# communication-hub.net
KiCad netlist of a schematic drawn in EAGLE
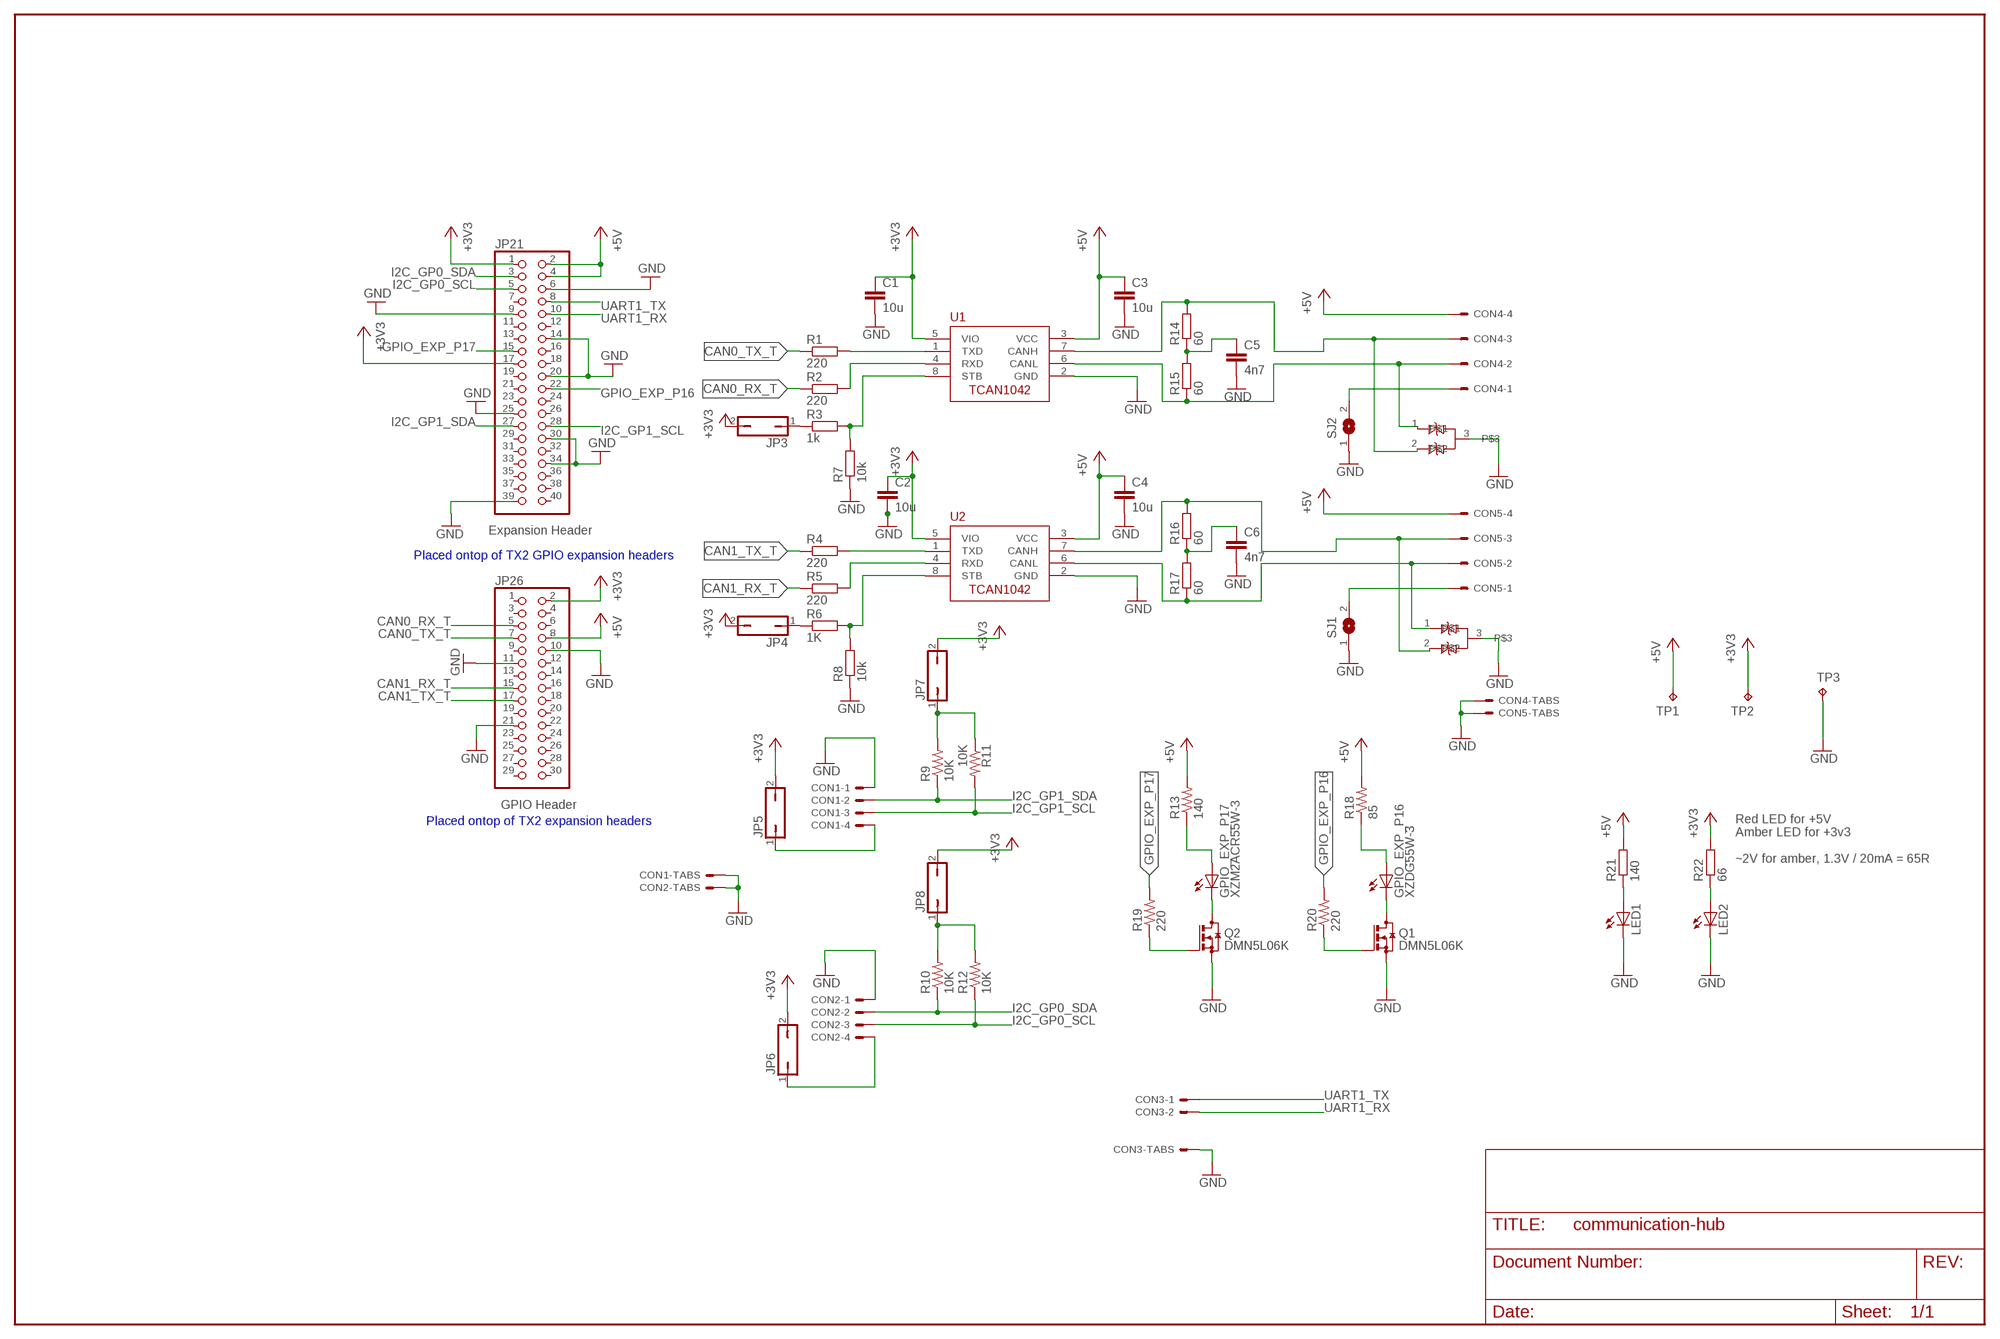
[diagram p0: schematic, sheet 1]

(export (version "E")
  (design (tool "Eeschema 10.0.6"))
  (components
    (comp (ref "C1")
      (value "10u")
      (footprint "eagle-import:C0805")
      (libsource (lib "eagle-import") (part "C-EUC0805"))
    )
    (comp (ref "C2")
      (value "10u")
      (footprint "eagle-import:C0805")
      (libsource (lib "eagle-import") (part "C-EUC0805"))
    )
    (comp (ref "C3")
      (value "10u")
      (footprint "eagle-import:C0805")
      (libsource (lib "eagle-import") (part "C-EUC0805"))
    )
    (comp (ref "C4")
      (value "10u")
      (footprint "eagle-import:C0805")
      (libsource (lib "eagle-import") (part "C-EUC0805"))
    )
    (comp (ref "C5")
      (value "4n7")
      (footprint "eagle-import:C0805")
      (libsource (lib "eagle-import") (part "C-EUC0805"))
    )
    (comp (ref "C6")
      (value "4n7")
      (footprint "eagle-import:C0805")
      (libsource (lib "eagle-import") (part "C-EUC0805"))
    )
    (comp (ref "CON1")
      (value "SM04B-GHS-TB")
      (footprint "eagle-import:SM04B-GHS-TB")
      (libsource (lib "eagle-import") (part "SM04B-GHS-TB"))
    )
    (comp (ref "CON2")
      (value "SM04B-GHS-TB")
      (footprint "eagle-import:SM04B-GHS-TB")
      (libsource (lib "eagle-import") (part "SM04B-GHS-TB"))
    )
    (comp (ref "CON3")
      (value "SM02B-GHS-TB")
      (footprint "eagle-import:SM02B-GHS-TB")
      (libsource (lib "eagle-import") (part "SM02B-GHS-TB"))
    )
    (comp (ref "CON4")
      (value "SM04B-GHS-TB")
      (footprint "eagle-import:SM04B-GHS-TB")
      (libsource (lib "eagle-import") (part "SM04B-GHS-TB"))
    )
    (comp (ref "CON5")
      (value "SM04B-GHS-TB")
      (footprint "eagle-import:SM04B-GHS-TB")
      (libsource (lib "eagle-import") (part "SM04B-GHS-TB"))
    )
    (comp (ref "GPIO_EXP_P16")
      (value "XZDG55W-3")
      (footprint "eagle-import:LED_1206")
      (libsource (lib "eagle-import") (part "LED_E"))
    )
    (comp (ref "GPIO_EXP_P17")
      (value "XZM2ACR55W-3")
      (footprint "eagle-import:LED_1206")
      (libsource (lib "eagle-import") (part "LED_E"))
    )
    (comp (ref "JP3")
      (value "JP1Q")
      (footprint "eagle-import:JP1")
      (libsource (lib "eagle-import") (part "JP1Q"))
    )
    (comp (ref "JP4")
      (value "JP1Q")
      (footprint "eagle-import:JP1")
      (libsource (lib "eagle-import") (part "JP1Q"))
    )
    (comp (ref "JP5")
      (value "JP1Q")
      (footprint "eagle-import:JP1")
      (libsource (lib "eagle-import") (part "JP1Q"))
    )
    (comp (ref "JP6")
      (value "JP1Q")
      (footprint "eagle-import:JP1")
      (libsource (lib "eagle-import") (part "JP1Q"))
    )
    (comp (ref "JP7")
      (value "JP1Q")
      (footprint "eagle-import:JP1")
      (libsource (lib "eagle-import") (part "JP1Q"))
    )
    (comp (ref "JP8")
      (value "JP1Q")
      (footprint "eagle-import:JP1")
      (libsource (lib "eagle-import") (part "JP1Q"))
    )
    (comp (ref "JP21")
      (value "PINHD-2X20")
      (footprint "eagle-import:2X20")
      (libsource (lib "eagle-import") (part "PINHD-2X20"))
    )
    (comp (ref "JP26")
      (value "PINHD-2X15")
      (footprint "eagle-import:2X15")
      (libsource (lib "eagle-import") (part "PINHD-2X15"))
    )
    (comp (ref "LED1")
      (value "LEDSMT1206")
      (footprint "eagle-import:1206")
      (libsource (lib "eagle-import") (part "LEDSMT1206"))
    )
    (comp (ref "LED2")
      (value "LEDSMT1206")
      (footprint "eagle-import:1206")
      (libsource (lib "eagle-import") (part "LEDSMT1206"))
    )
    (comp (ref "Q1")
      (value "DMN5L06K")
      (footprint "eagle-import:SOT23")
      (libsource (lib "eagle-import") (part "BSS123"))
    )
    (comp (ref "Q2")
      (value "DMN5L06K")
      (footprint "eagle-import:SOT23")
      (libsource (lib "eagle-import") (part "BSS123"))
    )
    (comp (ref "R1")
      (value "220")
      (footprint "eagle-import:R0805")
      (libsource (lib "eagle-import") (part "R-EU_R0805"))
    )
    (comp (ref "R2")
      (value "220")
      (footprint "eagle-import:R0805")
      (libsource (lib "eagle-import") (part "R-EU_R0805"))
    )
    (comp (ref "R3")
      (value "1k")
      (footprint "eagle-import:R0805")
      (libsource (lib "eagle-import") (part "R-EU_R0805"))
    )
    (comp (ref "R4")
      (value "220")
      (footprint "eagle-import:R0805")
      (libsource (lib "eagle-import") (part "R-EU_R0805"))
    )
    (comp (ref "R5")
      (value "220")
      (footprint "eagle-import:R0805")
      (libsource (lib "eagle-import") (part "R-EU_R0805"))
    )
    (comp (ref "R6")
      (value "1K")
      (footprint "eagle-import:R0805")
      (libsource (lib "eagle-import") (part "R-EU_R0805"))
    )
    (comp (ref "R7")
      (value "10k")
      (footprint "eagle-import:R0805")
      (libsource (lib "eagle-import") (part "R-EU_R0805"))
    )
    (comp (ref "R8")
      (value "10k")
      (footprint "eagle-import:R0805")
      (libsource (lib "eagle-import") (part "R-EU_R0805"))
    )
    (comp (ref "R9")
      (value "10K")
      (footprint "eagle-import:M1206")
      (libsource (lib "eagle-import") (part "resistor_348_R-US_M1206"))
    )
    (comp (ref "R10")
      (value "10K")
      (footprint "eagle-import:M1206")
      (libsource (lib "eagle-import") (part "resistor_348_R-US_M1206"))
    )
    (comp (ref "R11")
      (value "10K")
      (footprint "eagle-import:M1206")
      (libsource (lib "eagle-import") (part "resistor_348_R-US_M1206"))
    )
    (comp (ref "R12")
      (value "10K")
      (footprint "eagle-import:M1206")
      (libsource (lib "eagle-import") (part "resistor_348_R-US_M1206"))
    )
    (comp (ref "R13")
      (value "140")
      (footprint "eagle-import:M1206")
      (libsource (lib "eagle-import") (part "resistor_348_R-US_M1206"))
    )
    (comp (ref "R14")
      (value "60")
      (footprint "eagle-import:R1206")
      (libsource (lib "eagle-import") (part "R-EU_R1206"))
    )
    (comp (ref "R15")
      (value "60")
      (footprint "eagle-import:R1206")
      (libsource (lib "eagle-import") (part "R-EU_R1206"))
    )
    (comp (ref "R16")
      (value "60")
      (footprint "eagle-import:R1206")
      (libsource (lib "eagle-import") (part "R-EU_R1206"))
    )
    (comp (ref "R17")
      (value "60")
      (footprint "eagle-import:R1206")
      (libsource (lib "eagle-import") (part "R-EU_R1206"))
    )
    (comp (ref "R18")
      (value "85")
      (footprint "eagle-import:M1206")
      (libsource (lib "eagle-import") (part "resistor_348_R-US_M1206"))
    )
    (comp (ref "R19")
      (value "220")
      (footprint "eagle-import:R0805")
      (libsource (lib "eagle-import") (part "R-US_R0805"))
    )
    (comp (ref "R20")
      (value "220")
      (footprint "eagle-import:R0805")
      (libsource (lib "eagle-import") (part "R-US_R0805"))
    )
    (comp (ref "R21")
      (value "140")
      (footprint "eagle-import:R0805")
      (libsource (lib "eagle-import") (part "R-EU_R0805"))
    )
    (comp (ref "R22")
      (value "66")
      (footprint "eagle-import:R0805")
      (libsource (lib "eagle-import") (part "R-EU_R0805"))
    )
    (comp (ref "SJ1") (value "SJ") (footprint "eagle-import:SJ") (libsource (lib "eagle-import") (part "SJ")))
    (comp (ref "SJ2") (value "SJ") (footprint "eagle-import:SJ") (libsource (lib "eagle-import") (part "SJ")))
    (comp (ref "TP1")
      (value "TPB2,54")
      (footprint "eagle-import:B2,54")
      (libsource (lib "eagle-import") (part "TPB2,54"))
    )
    (comp (ref "TP2")
      (value "TPB2,54")
      (footprint "eagle-import:B2,54")
      (libsource (lib "eagle-import") (part "TPB2,54"))
    )
    (comp (ref "TP3")
      (value "TPB2,54")
      (footprint "eagle-import:B2,54")
      (libsource (lib "eagle-import") (part "TPB2,54"))
    )
    (comp (ref "U$4")
      (value "NUP2105L")
      (footprint "eagle-import:SOT23")
      (libsource (lib "eagle-import") (part "NUP2105L"))
    )
    (comp (ref "U$5")
      (value "NUP2105L")
      (footprint "eagle-import:SOT23")
      (libsource (lib "eagle-import") (part "NUP2105L"))
    )
    (comp (ref "U1")
      (value "TCAN1042HVDR")
      (footprint "eagle-import:SO-8")
      (libsource (lib "eagle-import") (part "TCAN1042HVDR"))
    )
    (comp (ref "U2")
      (value "TCAN1042HVDR")
      (footprint "eagle-import:SO-8")
      (libsource (lib "eagle-import") (part "TCAN1042HVDR"))
    )
  )
  (nets
    (net (code "1") (name "+3V3") (class "Default")
      (node (ref "C1") (pin "1") (pinfunction "1_1") (pintype "passive"))
      (node (ref "C2") (pin "1") (pinfunction "1_1") (pintype "passive"))
      (node (ref "JP21") (pin "1") (pinfunction "1_1") (pintype "passive"))
      (node (ref "JP21") (pin "17") (pinfunction "17_17") (pintype "passive"))
      (node (ref "JP26") (pin "2") (pinfunction "2_2") (pintype "passive"))
      (node (ref "JP3") (pin "2") (pinfunction "2_2") (pintype "passive"))
      (node (ref "JP4") (pin "2") (pinfunction "2_2") (pintype "passive"))
      (node (ref "JP5") (pin "2") (pinfunction "2_2") (pintype "passive"))
      (node (ref "JP6") (pin "2") (pinfunction "2_2") (pintype "passive"))
      (node (ref "JP7") (pin "2") (pinfunction "2_2") (pintype "passive"))
      (node (ref "JP8") (pin "2") (pinfunction "2_2") (pintype "passive"))
      (node (ref "R22") (pin "2") (pinfunction "2_2") (pintype "passive"))
      (node (ref "TP2") (pin "TP") (pinfunction "TP_TP") (pintype "input"))
      (node (ref "U1") (pin "5") (pinfunction "VIO_5") (pintype "bidirectional"))
      (node (ref "U2") (pin "5") (pinfunction "VIO_5") (pintype "bidirectional"))
    )
    (net (code "2") (name "+5V") (class "Default")
      (node (ref "C3") (pin "1") (pinfunction "1_1") (pintype "passive"))
      (node (ref "C4") (pin "1") (pinfunction "1_1") (pintype "passive"))
      (node (ref "CON4") (pin "P$4") (pinfunction "S_P$4") (pintype "passive"))
      (node (ref "CON5") (pin "P$4") (pinfunction "S_P$4") (pintype "passive"))
      (node (ref "JP21") (pin "2") (pinfunction "2_2") (pintype "passive"))
      (node (ref "JP21") (pin "4") (pinfunction "4_4") (pintype "passive"))
      (node (ref "JP26") (pin "8") (pinfunction "8_8") (pintype "passive"))
      (node (ref "R13") (pin "2") (pinfunction "2_2") (pintype "passive"))
      (node (ref "R18") (pin "2") (pinfunction "2_2") (pintype "passive"))
      (node (ref "R21") (pin "2") (pinfunction "2_2") (pintype "passive"))
      (node (ref "TP1") (pin "TP") (pinfunction "TP_TP") (pintype "input"))
      (node (ref "U1") (pin "3") (pinfunction "VCC_3") (pintype "bidirectional"))
      (node (ref "U2") (pin "3") (pinfunction "VCC_3") (pintype "bidirectional"))
    )
    (net (code "3") (name "/I2C_GP0_SCL") (class "Default")
      (node (ref "CON2") (pin "P$3") (pinfunction "S_P$3") (pintype "passive"))
      (node (ref "JP21") (pin "5") (pinfunction "5_5") (pintype "passive"))
      (node (ref "R12") (pin "1") (pinfunction "1_1") (pintype "passive"))
    )
    (net (code "4") (name "/I2C_GP0_SDA") (class "Default")
      (node (ref "CON2") (pin "P$2") (pinfunction "S_P$2") (pintype "passive"))
      (node (ref "JP21") (pin "3") (pinfunction "3_3") (pintype "passive"))
      (node (ref "R10") (pin "1") (pinfunction "1_1") (pintype "passive"))
    )
    (net (code "5") (name "/I2C_GP1_SCL") (class "Default")
      (node (ref "CON1") (pin "P$3") (pinfunction "S_P$3") (pintype "passive"))
      (node (ref "JP21") (pin "28") (pinfunction "28_28") (pintype "passive"))
      (node (ref "R11") (pin "2") (pinfunction "2_2") (pintype "passive"))
    )
    (net (code "6") (name "/I2C_GP1_SDA") (class "Default")
      (node (ref "CON1") (pin "P$2") (pinfunction "S_P$2") (pintype "passive"))
      (node (ref "JP21") (pin "27") (pinfunction "27_27") (pintype "passive"))
      (node (ref "R9") (pin "1") (pinfunction "1_1") (pintype "passive"))
    )
    (net (code "7") (name "/UART1_RX") (class "Default")
      (node (ref "CON3") (pin "P$2") (pinfunction "S_P$2") (pintype "passive"))
      (node (ref "JP21") (pin "10") (pinfunction "10_10") (pintype "passive"))
    )
    (net (code "8") (name "/UART1_TX") (class "Default")
      (node (ref "CON3") (pin "P$1") (pinfunction "S_P$1") (pintype "passive"))
      (node (ref "JP21") (pin "8") (pinfunction "8_8") (pintype "passive"))
    )
    (net (code "9") (name "CAN0_RX_T") (class "Default")
      (node (ref "JP26") (pin "5") (pinfunction "5_5") (pintype "passive"))
      (node (ref "R2") (pin "1") (pinfunction "1_1") (pintype "passive"))
    )
    (net (code "10") (name "CAN0_TX_T") (class "Default")
      (node (ref "JP26") (pin "7") (pinfunction "7_7") (pintype "passive"))
      (node (ref "R1") (pin "1") (pinfunction "1_1") (pintype "passive"))
    )
    (net (code "11") (name "CAN1_RX_T") (class "Default")
      (node (ref "JP26") (pin "15") (pinfunction "15_15") (pintype "passive"))
      (node (ref "R5") (pin "1") (pinfunction "1_1") (pintype "passive"))
    )
    (net (code "12") (name "CAN1_TX_T") (class "Default")
      (node (ref "JP26") (pin "17") (pinfunction "17_17") (pintype "passive"))
      (node (ref "R4") (pin "1") (pinfunction "1_1") (pintype "passive"))
    )
    (net (code "13") (name "GND") (class "Default")
      (node (ref "C1") (pin "2") (pinfunction "2_2") (pintype "passive"))
      (node (ref "C2") (pin "2") (pinfunction "2_2") (pintype "passive"))
      (node (ref "C3") (pin "2") (pinfunction "2_2") (pintype "passive"))
      (node (ref "C4") (pin "2") (pinfunction "2_2") (pintype "passive"))
      (node (ref "C5") (pin "2") (pinfunction "2_2") (pintype "passive"))
      (node (ref "C6") (pin "2") (pinfunction "2_2") (pintype "passive"))
      (node (ref "CON1") (pin "P$1") (pinfunction "S_P$1") (pintype "passive"))
      (node (ref "CON1") (pin "P$5") (pinfunction "S_P$5") (pintype "passive"))
      (node (ref "CON1") (pin "P$6") (pinfunction "S_P$6") (pintype "passive"))
      (node (ref "CON2") (pin "P$1") (pinfunction "S_P$1") (pintype "passive"))
      (node (ref "CON2") (pin "P$5") (pinfunction "S_P$5") (pintype "passive"))
      (node (ref "CON2") (pin "P$6") (pinfunction "S_P$6") (pintype "passive"))
      (node (ref "CON3") (pin "P$3") (pinfunction "S_P$3") (pintype "passive"))
      (node (ref "CON3") (pin "P$4") (pinfunction "S_P$4") (pintype "passive"))
      (node (ref "CON4") (pin "P$5") (pinfunction "S_P$5") (pintype "passive"))
      (node (ref "CON4") (pin "P$6") (pinfunction "S_P$6") (pintype "passive"))
      (node (ref "CON5") (pin "P$5") (pinfunction "S_P$5") (pintype "passive"))
      (node (ref "CON5") (pin "P$6") (pinfunction "S_P$6") (pintype "passive"))
      (node (ref "JP21") (pin "14") (pinfunction "14_14") (pintype "passive"))
      (node (ref "JP21") (pin "20") (pinfunction "20_20") (pintype "passive"))
      (node (ref "JP21") (pin "25") (pinfunction "25_25") (pintype "passive"))
      (node (ref "JP21") (pin "30") (pinfunction "30_30") (pintype "passive"))
      (node (ref "JP21") (pin "34") (pinfunction "34_34") (pintype "passive"))
      (node (ref "JP21") (pin "39") (pinfunction "39_39") (pintype "passive"))
      (node (ref "JP21") (pin "6") (pinfunction "6_6") (pintype "passive"))
      (node (ref "JP21") (pin "9") (pinfunction "9_9") (pintype "passive"))
      (node (ref "JP26") (pin "10") (pinfunction "10_10") (pintype "passive"))
      (node (ref "JP26") (pin "11") (pinfunction "11_11") (pintype "passive"))
      (node (ref "JP26") (pin "21") (pinfunction "21_21") (pintype "passive"))
      (node (ref "LED1") (pin "C") (pinfunction "C_C") (pintype "passive"))
      (node (ref "LED2") (pin "C") (pinfunction "C_C") (pintype "passive"))
      (node (ref "Q1") (pin "2") (pinfunction "S_2") (pintype "passive"))
      (node (ref "Q2") (pin "2") (pinfunction "S_2") (pintype "passive"))
      (node (ref "R7") (pin "1") (pinfunction "1_1") (pintype "passive"))
      (node (ref "R8") (pin "1") (pinfunction "1_1") (pintype "passive"))
      (node (ref "SJ1") (pin "1") (pinfunction "1_1") (pintype "passive"))
      (node (ref "SJ2") (pin "1") (pinfunction "1_1") (pintype "passive"))
      (node (ref "TP3") (pin "TP") (pinfunction "TP_TP") (pintype "input"))
      (node (ref "U$4") (pin "3") (pinfunction "P$3_3") (pintype "bidirectional"))
      (node (ref "U$5") (pin "3") (pinfunction "P$3_3") (pintype "bidirectional"))
      (node (ref "U1") (pin "2") (pinfunction "GND_2") (pintype "bidirectional"))
      (node (ref "U2") (pin "2") (pinfunction "GND_2") (pintype "bidirectional"))
    )
    (net (code "14") (name "GPIO_EXP_P16") (class "Default")
      (node (ref "JP21") (pin "22") (pinfunction "22_22") (pintype "passive"))
      (node (ref "R20") (pin "2") (pinfunction "2_2") (pintype "passive"))
    )
    (net (code "15") (name "GPIO_EXP_P17") (class "Default")
      (node (ref "JP21") (pin "15") (pinfunction "15_15") (pintype "passive"))
      (node (ref "R19") (pin "2") (pinfunction "2_2") (pintype "passive"))
    )
    (net (code "16") (name "Net-(C5-Pad1)") (class "Default")
      (node (ref "C5") (pin "1") (pinfunction "1_1") (pintype "passive"))
      (node (ref "R14") (pin "1") (pinfunction "1_1") (pintype "passive"))
      (node (ref "R15") (pin "2") (pinfunction "2_2") (pintype "passive"))
    )
    (net (code "17") (name "Net-(C6-Pad1)") (class "Default")
      (node (ref "C6") (pin "1") (pinfunction "1_1") (pintype "passive"))
      (node (ref "R16") (pin "1") (pinfunction "1_1") (pintype "passive"))
      (node (ref "R17") (pin "2") (pinfunction "2_2") (pintype "passive"))
    )
    (net (code "18") (name "Net-(CON1D-S)") (class "Default")
      (node (ref "CON1") (pin "P$4") (pinfunction "S_P$4") (pintype "passive"))
      (node (ref "JP5") (pin "1") (pinfunction "1_1") (pintype "passive"))
    )
    (net (code "19") (name "Net-(CON2D-S)") (class "Default")
      (node (ref "CON2") (pin "P$4") (pinfunction "S_P$4") (pintype "passive"))
      (node (ref "JP6") (pin "1") (pinfunction "1_1") (pintype "passive"))
    )
    (net (code "20") (name "Net-(CON4A-S)") (class "Default")
      (node (ref "CON4") (pin "P$1") (pinfunction "S_P$1") (pintype "passive"))
      (node (ref "SJ2") (pin "2") (pinfunction "2_2") (pintype "passive"))
    )
    (net (code "21") (name "Net-(CON4B-S)") (class "Default")
      (node (ref "CON4") (pin "P$2") (pinfunction "S_P$2") (pintype "passive"))
      (node (ref "R15") (pin "1") (pinfunction "1_1") (pintype "passive"))
      (node (ref "U$4") (pin "1") (pinfunction "P$1_1") (pintype "bidirectional"))
      (node (ref "U1") (pin "6") (pinfunction "CANL_6") (pintype "bidirectional"))
    )
    (net (code "22") (name "Net-(CON4C-S)") (class "Default")
      (node (ref "CON4") (pin "P$3") (pinfunction "S_P$3") (pintype "passive"))
      (node (ref "R14") (pin "2") (pinfunction "2_2") (pintype "passive"))
      (node (ref "U$4") (pin "2") (pinfunction "P$2_2") (pintype "bidirectional"))
      (node (ref "U1") (pin "7") (pinfunction "CANH_7") (pintype "bidirectional"))
    )
    (net (code "23") (name "Net-(CON5A-S)") (class "Default")
      (node (ref "CON5") (pin "P$1") (pinfunction "S_P$1") (pintype "passive"))
      (node (ref "SJ1") (pin "2") (pinfunction "2_2") (pintype "passive"))
    )
    (net (code "24") (name "Net-(CON5B-S)") (class "Default")
      (node (ref "CON5") (pin "P$2") (pinfunction "S_P$2") (pintype "passive"))
      (node (ref "R17") (pin "1") (pinfunction "1_1") (pintype "passive"))
      (node (ref "U$5") (pin "1") (pinfunction "P$1_1") (pintype "bidirectional"))
      (node (ref "U2") (pin "6") (pinfunction "CANL_6") (pintype "bidirectional"))
    )
    (net (code "25") (name "Net-(CON5C-S)") (class "Default")
      (node (ref "CON5") (pin "P$3") (pinfunction "S_P$3") (pintype "passive"))
      (node (ref "R16") (pin "2") (pinfunction "2_2") (pintype "passive"))
      (node (ref "U$5") (pin "2") (pinfunction "P$2_2") (pintype "bidirectional"))
      (node (ref "U2") (pin "7") (pinfunction "CANH_7") (pintype "bidirectional"))
    )
    (net (code "26") (name "Net-(GPIO_EXP_P16-PadA)") (class "Default")
      (node (ref "GPIO_EXP_P16") (pin "A") (pinfunction "A_A") (pintype "passive"))
      (node (ref "R18") (pin "1") (pinfunction "1_1") (pintype "passive"))
    )
    (net (code "27") (name "Net-(GPIO_EXP_P17-PadA)") (class "Default")
      (node (ref "GPIO_EXP_P17") (pin "A") (pinfunction "A_A") (pintype "passive"))
      (node (ref "R13") (pin "1") (pinfunction "1_1") (pintype "passive"))
    )
    (net (code "28") (name "Net-(JP3-Pad1)") (class "Default")
      (node (ref "JP3") (pin "1") (pinfunction "1_1") (pintype "passive"))
      (node (ref "R3") (pin "1") (pinfunction "1_1") (pintype "passive"))
    )
    (net (code "29") (name "Net-(JP4-Pad1)") (class "Default")
      (node (ref "JP4") (pin "1") (pinfunction "1_1") (pintype "passive"))
      (node (ref "R6") (pin "1") (pinfunction "1_1") (pintype "passive"))
    )
    (net (code "30") (name "Net-(JP7-Pad1)") (class "Default")
      (node (ref "JP7") (pin "1") (pinfunction "1_1") (pintype "passive"))
      (node (ref "R11") (pin "1") (pinfunction "1_1") (pintype "passive"))
      (node (ref "R9") (pin "2") (pinfunction "2_2") (pintype "passive"))
    )
    (net (code "31") (name "Net-(JP8-Pad1)") (class "Default")
      (node (ref "JP8") (pin "1") (pinfunction "1_1") (pintype "passive"))
      (node (ref "R10") (pin "2") (pinfunction "2_2") (pintype "passive"))
      (node (ref "R12") (pin "2") (pinfunction "2_2") (pintype "passive"))
    )
    (net (code "32") (name "Net-(LED1-PadA)") (class "Default")
      (node (ref "LED1") (pin "A") (pinfunction "A_A") (pintype "passive"))
      (node (ref "R21") (pin "1") (pinfunction "1_1") (pintype "passive"))
    )
    (net (code "33") (name "Net-(LED2-PadA)") (class "Default")
      (node (ref "LED2") (pin "A") (pinfunction "A_A") (pintype "passive"))
      (node (ref "R22") (pin "1") (pinfunction "1_1") (pintype "passive"))
    )
    (net (code "34") (name "Net-(Q1-D)") (class "Default")
      (node (ref "GPIO_EXP_P16") (pin "C") (pinfunction "C_C") (pintype "passive"))
      (node (ref "Q1") (pin "3") (pinfunction "D_3") (pintype "passive"))
    )
    (net (code "35") (name "Net-(Q1-G)") (class "Default")
      (node (ref "Q1") (pin "1") (pinfunction "G_1") (pintype "passive"))
      (node (ref "R20") (pin "1") (pinfunction "1_1") (pintype "passive"))
    )
    (net (code "36") (name "Net-(Q2-D)") (class "Default")
      (node (ref "GPIO_EXP_P17") (pin "C") (pinfunction "C_C") (pintype "passive"))
      (node (ref "Q2") (pin "3") (pinfunction "D_3") (pintype "passive"))
    )
    (net (code "37") (name "Net-(Q2-G)") (class "Default")
      (node (ref "Q2") (pin "1") (pinfunction "G_1") (pintype "passive"))
      (node (ref "R19") (pin "1") (pinfunction "1_1") (pintype "passive"))
    )
    (net (code "38") (name "Net-(U1-RXD)") (class "Default")
      (node (ref "R2") (pin "2") (pinfunction "2_2") (pintype "passive"))
      (node (ref "U1") (pin "4") (pinfunction "RXD_4") (pintype "bidirectional"))
    )
    (net (code "39") (name "Net-(U1-STB)") (class "Default")
      (node (ref "R3") (pin "2") (pinfunction "2_2") (pintype "passive"))
      (node (ref "R7") (pin "2") (pinfunction "2_2") (pintype "passive"))
      (node (ref "U1") (pin "8") (pinfunction "STB_8") (pintype "bidirectional"))
    )
    (net (code "40") (name "Net-(U1-TXD)") (class "Default")
      (node (ref "R1") (pin "2") (pinfunction "2_2") (pintype "passive"))
      (node (ref "U1") (pin "1") (pinfunction "TXD_1") (pintype "bidirectional"))
    )
    (net (code "41") (name "Net-(U2-RXD)") (class "Default")
      (node (ref "R5") (pin "2") (pinfunction "2_2") (pintype "passive"))
      (node (ref "U2") (pin "4") (pinfunction "RXD_4") (pintype "bidirectional"))
    )
    (net (code "42") (name "Net-(U2-STB)") (class "Default")
      (node (ref "R6") (pin "2") (pinfunction "2_2") (pintype "passive"))
      (node (ref "R8") (pin "2") (pinfunction "2_2") (pintype "passive"))
      (node (ref "U2") (pin "8") (pinfunction "STB_8") (pintype "bidirectional"))
    )
    (net (code "43") (name "Net-(U2-TXD)") (class "Default")
      (node (ref "R4") (pin "2") (pinfunction "2_2") (pintype "passive"))
      (node (ref "U2") (pin "1") (pinfunction "TXD_1") (pintype "bidirectional"))
    )
    (net (code "44") (name "unconnected-(JP21-Pad7)") (class "Default")
      (node (ref "JP21") (pin "7") (pinfunction "7_7") (pintype "passive"))
    )
    (net (code "45") (name "unconnected-(JP21-Pad11)") (class "Default")
      (node (ref "JP21") (pin "11") (pinfunction "11_11") (pintype "passive"))
    )
    (net (code "46") (name "unconnected-(JP21-Pad12)") (class "Default")
      (node (ref "JP21") (pin "12") (pinfunction "12_12") (pintype "passive"))
    )
    (net (code "47") (name "unconnected-(JP21-Pad13)") (class "Default")
      (node (ref "JP21") (pin "13") (pinfunction "13_13") (pintype "passive"))
    )
    (net (code "48") (name "unconnected-(JP21-Pad16)") (class "Default")
      (node (ref "JP21") (pin "16") (pinfunction "16_16") (pintype "passive"))
    )
    (net (code "49") (name "unconnected-(JP21-Pad18)") (class "Default")
      (node (ref "JP21") (pin "18") (pinfunction "18_18") (pintype "passive"))
    )
    (net (code "50") (name "unconnected-(JP21-Pad19)") (class "Default")
      (node (ref "JP21") (pin "19") (pinfunction "19_19") (pintype "passive"))
    )
    (net (code "51") (name "unconnected-(JP21-Pad21)") (class "Default")
      (node (ref "JP21") (pin "21") (pinfunction "21_21") (pintype "passive"))
    )
    (net (code "52") (name "unconnected-(JP21-Pad23)") (class "Default")
      (node (ref "JP21") (pin "23") (pinfunction "23_23") (pintype "passive"))
    )
    (net (code "53") (name "unconnected-(JP21-Pad24)") (class "Default")
      (node (ref "JP21") (pin "24") (pinfunction "24_24") (pintype "passive"))
    )
    (net (code "54") (name "unconnected-(JP21-Pad26)") (class "Default")
      (node (ref "JP21") (pin "26") (pinfunction "26_26") (pintype "passive"))
    )
    (net (code "55") (name "unconnected-(JP21-Pad29)") (class "Default")
      (node (ref "JP21") (pin "29") (pinfunction "29_29") (pintype "passive"))
    )
    (net (code "56") (name "unconnected-(JP21-Pad31)") (class "Default")
      (node (ref "JP21") (pin "31") (pinfunction "31_31") (pintype "passive"))
    )
    (net (code "57") (name "unconnected-(JP21-Pad32)") (class "Default")
      (node (ref "JP21") (pin "32") (pinfunction "32_32") (pintype "passive"))
    )
    (net (code "58") (name "unconnected-(JP21-Pad33)") (class "Default")
      (node (ref "JP21") (pin "33") (pinfunction "33_33") (pintype "passive"))
    )
    (net (code "59") (name "unconnected-(JP21-Pad35)") (class "Default")
      (node (ref "JP21") (pin "35") (pinfunction "35_35") (pintype "passive"))
    )
    (net (code "60") (name "unconnected-(JP21-Pad36)") (class "Default")
      (node (ref "JP21") (pin "36") (pinfunction "36_36") (pintype "passive"))
    )
    (net (code "61") (name "unconnected-(JP21-Pad37)") (class "Default")
      (node (ref "JP21") (pin "37") (pinfunction "37_37") (pintype "passive"))
    )
    (net (code "62") (name "unconnected-(JP21-Pad38)") (class "Default")
      (node (ref "JP21") (pin "38") (pinfunction "38_38") (pintype "passive"))
    )
    (net (code "63") (name "unconnected-(JP21-Pad40)") (class "Default")
      (node (ref "JP21") (pin "40") (pinfunction "40_40") (pintype "passive"))
    )
    (net (code "64") (name "unconnected-(JP26-Pad1)") (class "Default")
      (node (ref "JP26") (pin "1") (pinfunction "1_1") (pintype "passive"))
    )
    (net (code "65") (name "unconnected-(JP26-Pad3)") (class "Default")
      (node (ref "JP26") (pin "3") (pinfunction "3_3") (pintype "passive"))
    )
    (net (code "66") (name "unconnected-(JP26-Pad4)") (class "Default")
      (node (ref "JP26") (pin "4") (pinfunction "4_4") (pintype "passive"))
    )
    (net (code "67") (name "unconnected-(JP26-Pad6)") (class "Default")
      (node (ref "JP26") (pin "6") (pinfunction "6_6") (pintype "passive"))
    )
    (net (code "68") (name "unconnected-(JP26-Pad9)") (class "Default")
      (node (ref "JP26") (pin "9") (pinfunction "9_9") (pintype "passive"))
    )
    (net (code "69") (name "unconnected-(JP26-Pad12)") (class "Default")
      (node (ref "JP26") (pin "12") (pinfunction "12_12") (pintype "passive"))
    )
    (net (code "70") (name "unconnected-(JP26-Pad13)") (class "Default")
      (node (ref "JP26") (pin "13") (pinfunction "13_13") (pintype "passive"))
    )
    (net (code "71") (name "unconnected-(JP26-Pad14)") (class "Default")
      (node (ref "JP26") (pin "14") (pinfunction "14_14") (pintype "passive"))
    )
    (net (code "72") (name "unconnected-(JP26-Pad16)") (class "Default")
      (node (ref "JP26") (pin "16") (pinfunction "16_16") (pintype "passive"))
    )
    (net (code "73") (name "unconnected-(JP26-Pad18)") (class "Default")
      (node (ref "JP26") (pin "18") (pinfunction "18_18") (pintype "passive"))
    )
    (net (code "74") (name "unconnected-(JP26-Pad19)") (class "Default")
      (node (ref "JP26") (pin "19") (pinfunction "19_19") (pintype "passive"))
    )
    (net (code "75") (name "unconnected-(JP26-Pad20)") (class "Default")
      (node (ref "JP26") (pin "20") (pinfunction "20_20") (pintype "passive"))
    )
    (net (code "76") (name "unconnected-(JP26-Pad22)") (class "Default")
      (node (ref "JP26") (pin "22") (pinfunction "22_22") (pintype "passive"))
    )
    (net (code "77") (name "unconnected-(JP26-Pad23)") (class "Default")
      (node (ref "JP26") (pin "23") (pinfunction "23_23") (pintype "passive"))
    )
    (net (code "78") (name "unconnected-(JP26-Pad24)") (class "Default")
      (node (ref "JP26") (pin "24") (pinfunction "24_24") (pintype "passive"))
    )
    (net (code "79") (name "unconnected-(JP26-Pad25)") (class "Default")
      (node (ref "JP26") (pin "25") (pinfunction "25_25") (pintype "passive"))
    )
    (net (code "80") (name "unconnected-(JP26-Pad26)") (class "Default")
      (node (ref "JP26") (pin "26") (pinfunction "26_26") (pintype "passive"))
    )
    (net (code "81") (name "unconnected-(JP26-Pad27)") (class "Default")
      (node (ref "JP26") (pin "27") (pinfunction "27_27") (pintype "passive"))
    )
    (net (code "82") (name "unconnected-(JP26-Pad28)") (class "Default")
      (node (ref "JP26") (pin "28") (pinfunction "28_28") (pintype "passive"))
    )
    (net (code "83") (name "unconnected-(JP26-Pad29)") (class "Default")
      (node (ref "JP26") (pin "29") (pinfunction "29_29") (pintype "passive"))
    )
    (net (code "84") (name "unconnected-(JP26-Pad30)") (class "Default")
      (node (ref "JP26") (pin "30") (pinfunction "30_30") (pintype "passive"))
    )
  )
)
